# SCH_LM386-AMP-MONO_2026-03-15.net
KiCad netlist of a schematic drawn in EasyEDA
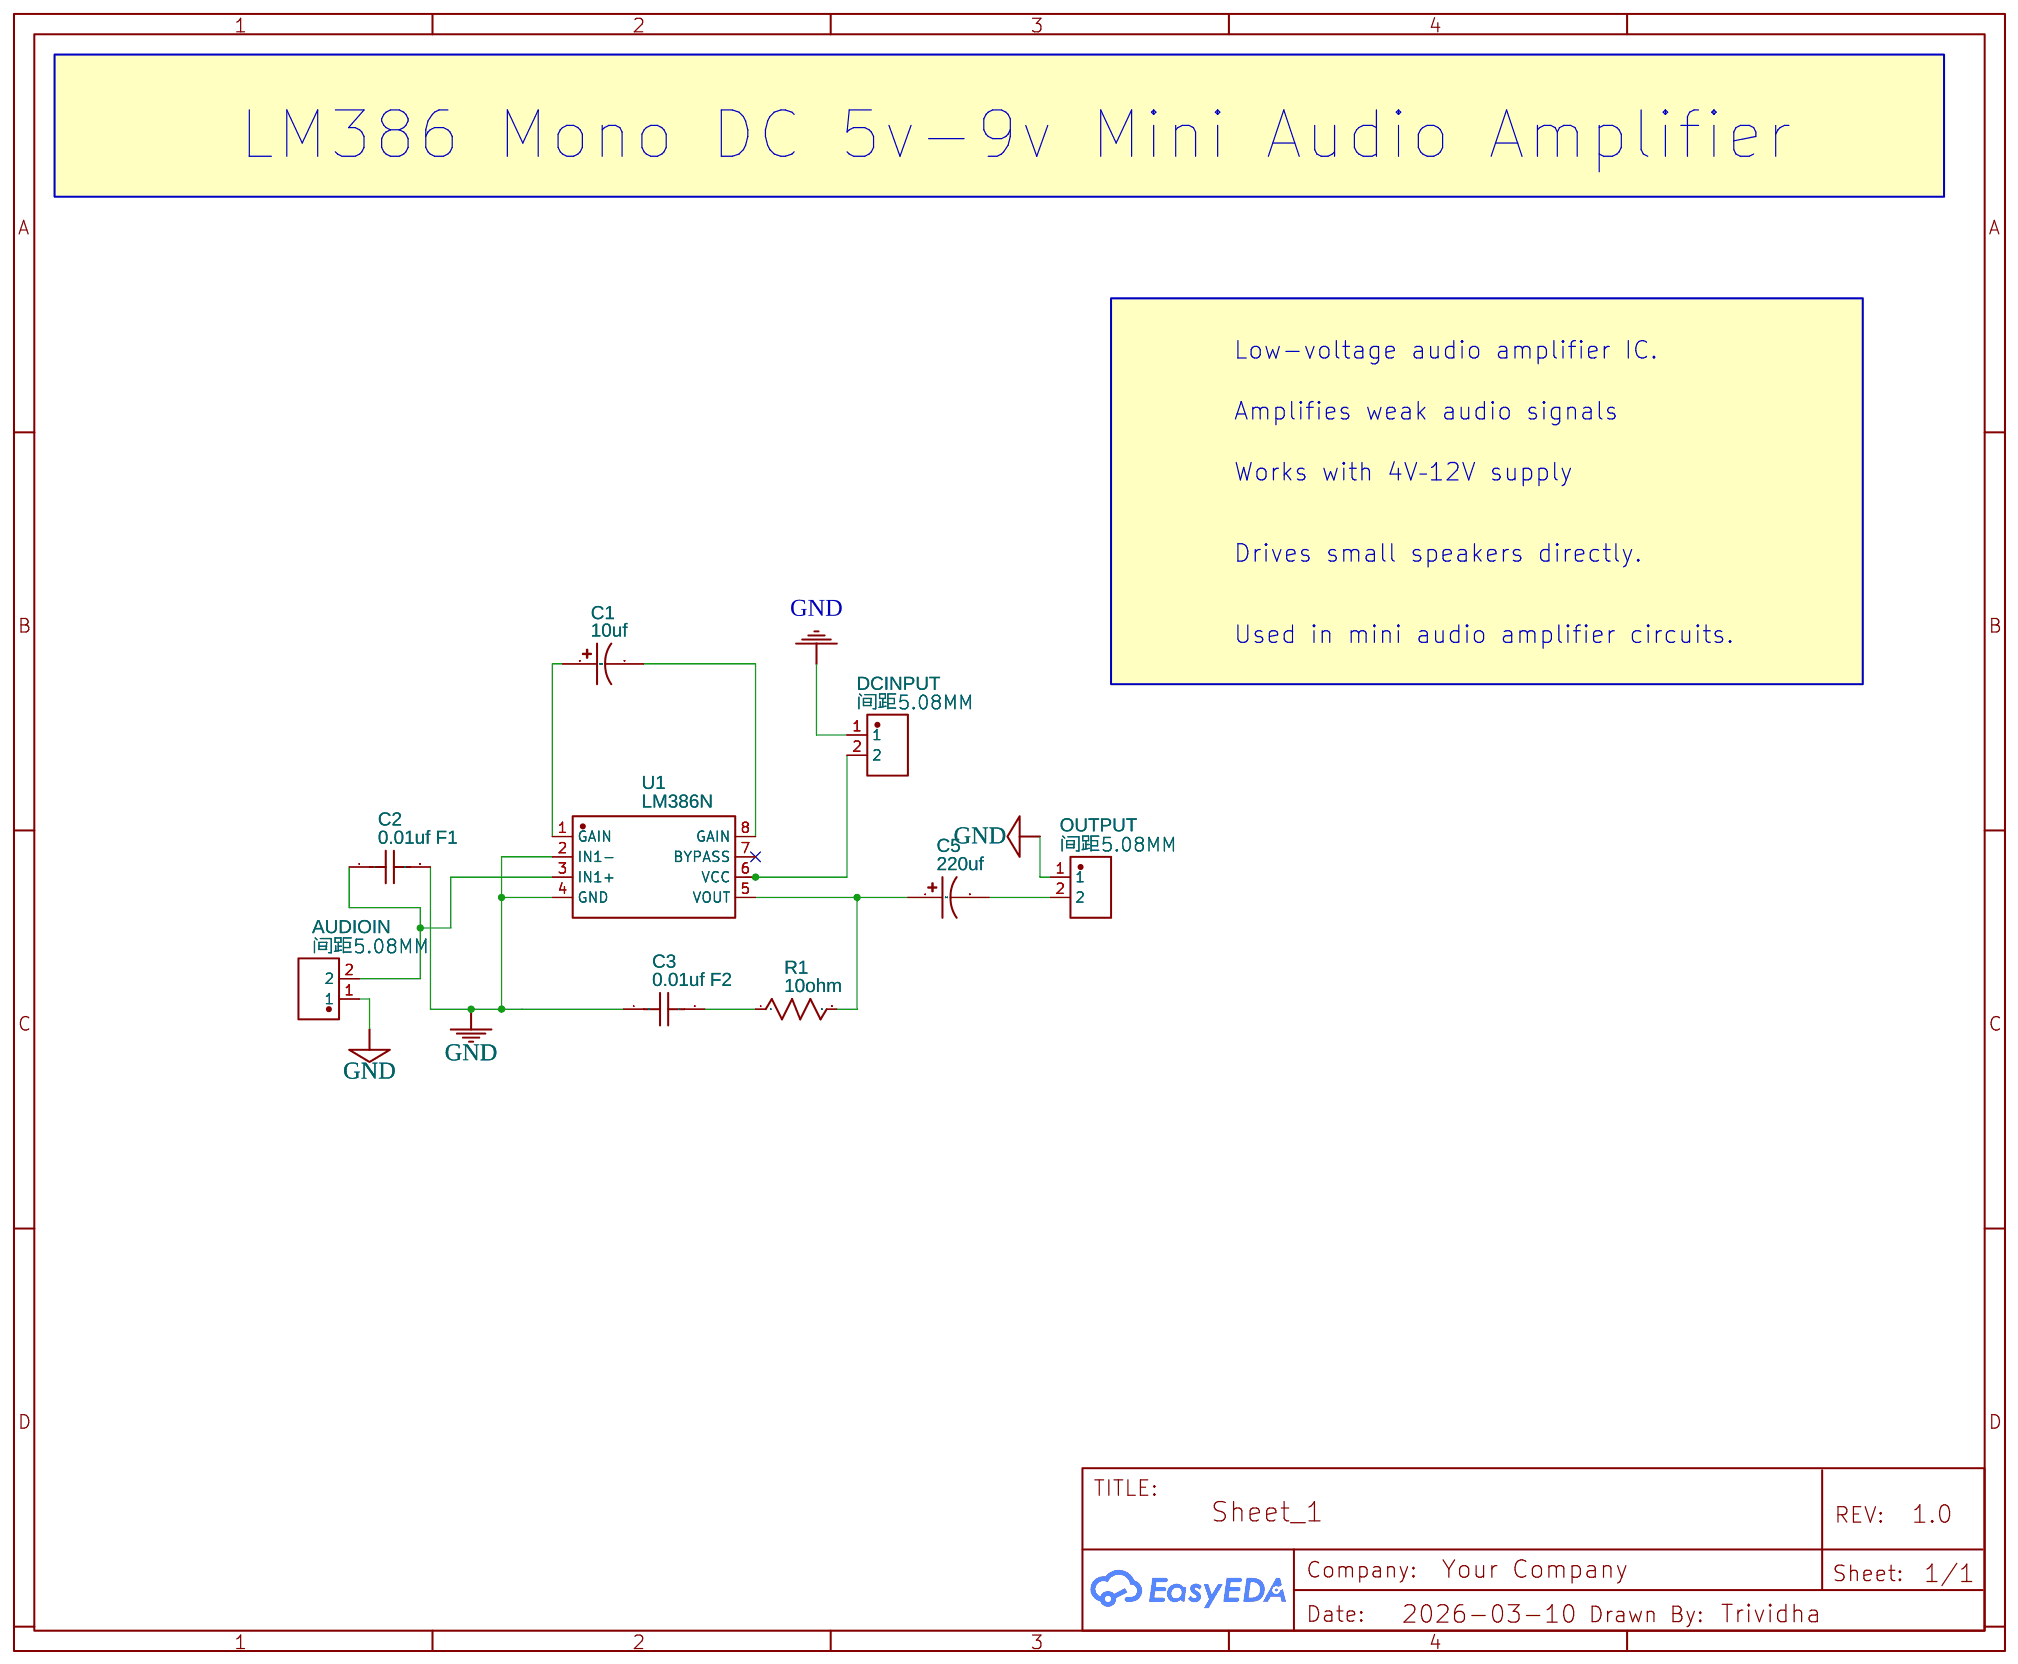
[diagram p0: schematic sheet]

(export (version "E")
  (design (tool "Eeschema 10.0.6"))
  (components
    (comp (ref "AUDIOIN") (value "间距5.08MM") (libsource (lib "") (part "间距5.08MM_1")))
    (comp (ref "C1") (value "10uf") (libsource (lib "") (part "C_Tan_SMD_A_US")))
    (comp (ref "C2") (value "0.01uf F1") (libsource (lib "") (part "C_0603_US")))
    (comp (ref "C3") (value "0.01uf F2") (libsource (lib "") (part "C_RAD-0.1_US")))
    (comp (ref "C5") (value "220uf") (libsource (lib "") (part "C_Tan_SMD_A_US")))
    (comp (ref "DCINPUT") (value "间距5.08MM") (libsource (lib "") (part "间距5.08MM_2")))
    (comp (ref "OUTPUT") (value "间距5.08MM") (libsource (lib "") (part "间距5.08MM")))
    (comp (ref "R1") (value "10ohm") (libsource (lib "") (part "R_AXIAL-0.3_US")))
    (comp (ref "U1")
      (value "LM386N")
      (fields (field (name "Manufacturer") "HTC"))
      (libsource (lib "") (part "LM386N"))
    )
  )
  (nets
    (net (code "1") (name "GND") (class "Default")
      (node (ref "AUDIOIN") (pin "1") (pinfunction "1_1") (pintype "unspecified"))
      (node (ref "C2") (pin "2") (pinfunction "2_2") (pintype "unspecified"))
      (node (ref "C3") (pin "1") (pinfunction "1_1") (pintype "unspecified"))
      (node (ref "DCINPUT") (pin "1") (pinfunction "1_1") (pintype "unspecified"))
      (node (ref "OUTPUT") (pin "1") (pinfunction "1_1") (pintype "unspecified"))
      (node (ref "U1") (pin "2") (pinfunction "IN1-_2") (pintype "unspecified"))
      (node (ref "U1") (pin "4") (pinfunction "GND_4") (pintype "unspecified"))
    )
    (net (code "2") (name "Net-(C1-Pad1)") (class "Default")
      (node (ref "C1") (pin "1") (pinfunction "1_1") (pintype "unspecified"))
      (node (ref "U1") (pin "1") (pinfunction "GAIN_1") (pintype "unspecified"))
    )
    (net (code "3") (name "Net-(C1-Pad2)") (class "Default")
      (node (ref "C1") (pin "2") (pinfunction "2_2") (pintype "unspecified"))
      (node (ref "U1") (pin "8") (pinfunction "GAIN_8") (pintype "unspecified"))
    )
    (net (code "4") (name "Net-(C3-Pad2)") (class "Default")
      (node (ref "C3") (pin "2") (pinfunction "2_2") (pintype "unspecified"))
      (node (ref "R1") (pin "1") (pinfunction "1_1") (pintype "unspecified"))
    )
    (net (code "5") (name "Net-(C5-Pad2)") (class "Default")
      (node (ref "C5") (pin "2") (pinfunction "2_2") (pintype "unspecified"))
      (node (ref "OUTPUT") (pin "2") (pinfunction "2_2") (pintype "unspecified"))
    )
    (net (code "6") (name "Net-(U1-IN1+)") (class "Default")
      (node (ref "AUDIOIN") (pin "2") (pinfunction "2_2") (pintype "unspecified"))
      (node (ref "C2") (pin "1") (pinfunction "1_1") (pintype "unspecified"))
      (node (ref "U1") (pin "3") (pinfunction "IN1+_3") (pintype "unspecified"))
    )
    (net (code "7") (name "Net-(U1-VCC)") (class "Default")
      (node (ref "DCINPUT") (pin "2") (pinfunction "2_2") (pintype "unspecified"))
      (node (ref "U1") (pin "6") (pinfunction "VCC_6") (pintype "unspecified"))
    )
    (net (code "8") (name "Net-(U1-VOUT)") (class "Default")
      (node (ref "C5") (pin "1") (pinfunction "1_1") (pintype "unspecified"))
      (node (ref "R1") (pin "2") (pinfunction "2_2") (pintype "unspecified"))
      (node (ref "U1") (pin "5") (pinfunction "VOUT_5") (pintype "unspecified"))
    )
    (net (code "9") (name "unconnected-(U1-BYPASS-Pad7)") (class "Default")
      (node (ref "U1") (pin "7") (pinfunction "BYPASS_7") (pintype "unspecified+no_connect"))
    )
  )
)
